# Power_Supply.net
KiCad netlist of a schematic drawn in Altium Designer
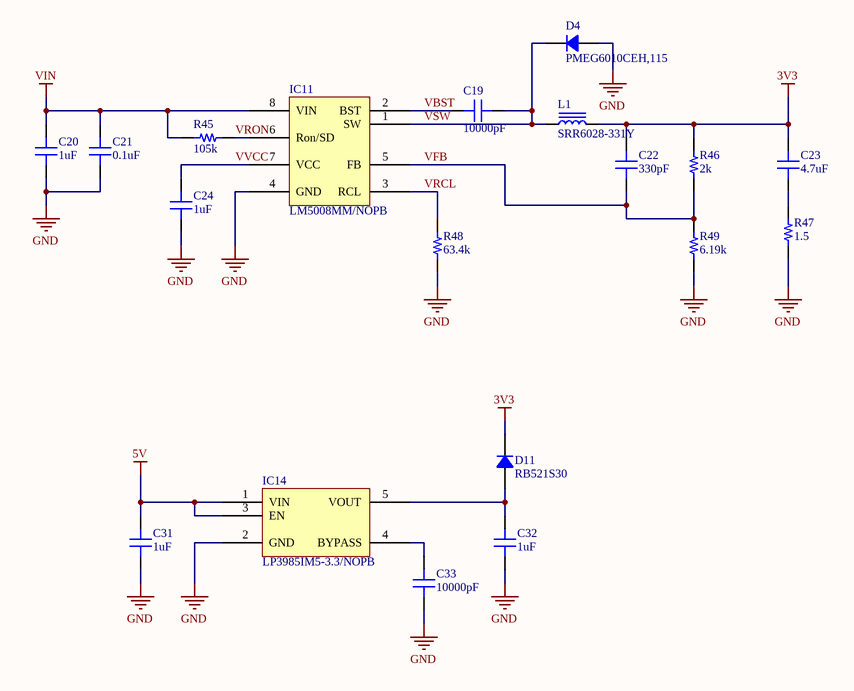
[diagram p0: Power Supply.SchDoc]

(export (version "E")
  (design (tool "Eeschema 10.0.6"))
  (components
    (comp (ref "C19")
      (value "10000pF")
      (footprint "CAP 0603/1608")
      (description "CAP CER 10000PF 50V X7R 0603")
      (fields
        (field (name "PART NUMBER") "CL10B103KB8NCNC")
        (field (name "MANUFACTURER") "Samsung Electro-Mechanics America, Inc.")
      )
      (libsource (lib "Celestial Library Database") (part "Capacitor"))
    )
    (comp (ref "C20")
      (value "1uF")
      (footprint "CAP 0603/1608")
      (description "CAP CER 1UF 50V X5R 0603")
      (fields
        (field (name "PART NUMBER") "CL10A105KB8NNNC")
        (field (name "MANUFACTURER") "Samsung Electro-Mechanics America, Inc.")
      )
      (libsource (lib "Celestial Library Database") (part "Capacitor"))
    )
    (comp (ref "C21")
      (value "0.1uF")
      (footprint "CAP 0603/1608")
      (description "CAP CER 0.1UF 50V X7R 0603")
      (fields
        (field (name "PART NUMBER") "CL10B104JB8NNNC")
        (field (name "MANUFACTURER") "Samsung Electro-Mechanics America, Inc.")
      )
      (libsource (lib "Celestial Library Database") (part "Capacitor"))
    )
    (comp (ref "C22")
      (value "330pF")
      (footprint "CAP 0603/1608")
      (description "CAP CER 330PF 50V NP0 0603")
      (fields (field (name "PART NUMBER") "C0603C331J5GACTU") (field (name "MANUFACTURER") "Kemet"))
      (libsource (lib "Celestial Library Database") (part "Capacitor"))
    )
    (comp (ref "C23")
      (value "4.7uF")
      (footprint "CAP 0603/1608")
      (description "CAP CER 4.7UF 6.3V X5R 0603")
      (fields
        (field (name "PART NUMBER") "CL10A475KQ8NNNC")
        (field (name "MANUFACTURER") "Samsung Electro-Mechanics America, Inc.")
      )
      (libsource (lib "Celestial Library Database") (part "Capacitor"))
    )
    (comp (ref "C24")
      (value "1uF")
      (footprint "CAP 0603/1608")
      (description "CAP CER 1UF 50V X5R 0603")
      (fields
        (field (name "PART NUMBER") "CL10A105KB8NNNC")
        (field (name "MANUFACTURER") "Samsung Electro-Mechanics America, Inc.")
      )
      (libsource (lib "Celestial Library Database") (part "Capacitor"))
    )
    (comp (ref "C31")
      (value "1uF")
      (footprint "CAP 0603/1608")
      (description "CAP CER 1UF 50V X5R 0603")
      (fields
        (field (name "PART NUMBER") "CL10A105KB8NNNC")
        (field (name "MANUFACTURER") "Samsung Electro-Mechanics America, Inc.")
      )
      (libsource (lib "Celestial Library Database") (part "Capacitor"))
    )
    (comp (ref "C32")
      (value "1uF")
      (footprint "CAP 0603/1608")
      (description "CAP CER 1UF 50V X5R 0603")
      (fields
        (field (name "PART NUMBER") "CL10A105KB8NNNC")
        (field (name "MANUFACTURER") "Samsung Electro-Mechanics America, Inc.")
      )
      (libsource (lib "Celestial Library Database") (part "Capacitor"))
    )
    (comp (ref "C33")
      (value "10000pF")
      (footprint "CAP 0603/1608")
      (description "CAP CER 10000PF 50V X7R 0603")
      (fields
        (field (name "PART NUMBER") "CL10B103KB8NCNC")
        (field (name "MANUFACTURER") "Samsung Electro-Mechanics America, Inc.")
      )
      (libsource (lib "Celestial Library Database") (part "Capacitor"))
    )
    (comp (ref "D4")
      (value "PMEG6010CEH,115")
      (footprint "SOD123F")
      (description "DIODE SCHOTTKY 60V 1A SOD123F")
      (fields (field (name "MANUFACTURER") "NXP USA Inc."))
      (libsource (lib "Celestial Library Database") (part "Diode"))
    )
    (comp (ref "D11")
      (value "RB521S30")
      (footprint "SOD523F")
      (description "DIODE SCHOTTKY 30V 200MA SOD523F")
      (fields (field (name "MANUFACTURER") "Fairchild Semiconductor"))
      (libsource (lib "Celestial Library Database") (part "Diode"))
    )
    (comp (ref "IC11")
      (value "LM5008MM/NOPB")
      (footprint "TI VSSOP-8 DGK")
      (description "IC REG BUCK ADJ 0.35A 8VSSOP")
      (fields (field (name "MANUFACTURER") "Texas Instruments"))
      (libsource (lib "Celestial Library Database") (part "TI LM5008"))
    )
    (comp (ref "IC14")
      (value "LP3985IM5-3.3/NOPB")
      (footprint "TI SOT-23-5 DBV")
      (description "IC REG LDO 3.3V 0.15A SOT23-5")
      (fields (field (name "MANUFACTURER") "Texas Instruments"))
      (libsource (lib "Celestial Library Database") (part "TI LP3985"))
    )
    (comp (ref "L1")
      (value "SRR6028-331Y")
      (footprint "BOURNS SRR6028")
      (description "FIXED IND 330UH 370MA 1.4 OHM")
      (fields (field (name "MANUFACTURER") "Bourns Inc.") (field (name "TOLERANCE") "30%"))
      (libsource (lib "Celestial Library Database") (part "Inductor"))
    )
    (comp (ref "R45")
      (value "105k")
      (footprint "RES 0603/1608")
      (description "RES SMD 105K OHM 1% 1/10W 0603")
      (fields
        (field (name "PART NUMBER") "ERJ-3EKF1053V")
        (field (name "MANUFACTURER") "Panasonic Electronic Components")
      )
      (libsource (lib "Celestial Library Database") (part "Resistor"))
    )
    (comp (ref "R46")
      (value "2k")
      (footprint "RES 0603/1608")
      (description "RES SMD 2K OHM 5% 1/10W 0603")
      (fields
        (field (name "PART NUMBER") "ERJ-3GEYJ202V")
        (field (name "MANUFACTURER") "Panasonic Electronic Components")
      )
      (libsource (lib "Celestial Library Database") (part "Resistor"))
    )
    (comp (ref "R47")
      (value "1.5")
      (footprint "RES 0603/1608")
      (description "RES SMD 1.5 OHM 5% 1/10W 0603")
      (fields
        (field (name "PART NUMBER") "ERJ-3GEYJ1R5V")
        (field (name "MANUFACTURER") "Panasonic Electronic Components")
      )
      (libsource (lib "Celestial Library Database") (part "Resistor"))
    )
    (comp (ref "R48")
      (value "63.4k")
      (footprint "RES 0603/1608")
      (description "RES SMD 63.4K OHM 1% 1/10W 0603")
      (fields
        (field (name "PART NUMBER") "ERJ-3EKF6342V")
        (field (name "MANUFACTURER") "Panasonic Electronic Components")
      )
      (libsource (lib "Celestial Library Database") (part "Resistor"))
    )
    (comp (ref "R49")
      (value "6.19k")
      (footprint "RES 0603/1608")
      (description "RES SMD 6.19K OHM 1% 1/10W 0603")
      (fields
        (field (name "PART NUMBER") "ERJ-3EKF6191V")
        (field (name "MANUFACTURER") "Panasonic Electronic Components")
      )
      (libsource (lib "Celestial Library Database") (part "Resistor"))
    )
  )
  (nets
    (net (code "1") (name "/VBST") (class "Default")
      (node (ref "C19") (pin "2") (pinfunction "2_2") (pintype "passive"))
      (node (ref "IC11") (pin "2") (pinfunction "BST_2") (pintype "passive"))
    )
    (net (code "2") (name "/VFB") (class "Default")
      (node (ref "C22") (pin "1") (pinfunction "1_1") (pintype "passive"))
      (node (ref "IC11") (pin "5") (pinfunction "FB_5") (pintype "passive"))
      (node (ref "R46") (pin "2") (pinfunction "2_2") (pintype "passive"))
      (node (ref "R49") (pin "2") (pinfunction "2_2") (pintype "passive"))
    )
    (net (code "3") (name "/VRCL") (class "Default")
      (node (ref "IC11") (pin "3") (pinfunction "RCL_3") (pintype "passive"))
      (node (ref "R48") (pin "2") (pinfunction "2_2") (pintype "passive"))
    )
    (net (code "4") (name "/VRON") (class "Default")
      (node (ref "IC11") (pin "6") (pinfunction "Ron/SD_6") (pintype "passive"))
      (node (ref "R45") (pin "2") (pinfunction "2_2") (pintype "passive"))
    )
    (net (code "5") (name "/VSW") (class "Default")
      (node (ref "C19") (pin "1") (pinfunction "1_1") (pintype "passive"))
      (node (ref "D4") (pin "2") (pinfunction "2_2") (pintype "passive"))
      (node (ref "IC11") (pin "1") (pinfunction "SW_1") (pintype "passive"))
      (node (ref "L1") (pin "1") (pinfunction "1_1") (pintype "passive"))
    )
    (net (code "6") (name "/VVCC") (class "Default")
      (node (ref "C24") (pin "2") (pinfunction "2_2") (pintype "passive"))
      (node (ref "IC11") (pin "7") (pinfunction "VCC_7") (pintype "passive"))
    )
    (net (code "7") (name "3V3") (class "Default")
      (node (ref "C22") (pin "2") (pinfunction "2_2") (pintype "passive"))
      (node (ref "C23") (pin "2") (pinfunction "2_2") (pintype "passive"))
      (node (ref "D11") (pin "2") (pinfunction "2_2") (pintype "passive"))
      (node (ref "L1") (pin "2") (pinfunction "2_2") (pintype "passive"))
      (node (ref "R46") (pin "1") (pinfunction "1_1") (pintype "passive"))
    )
    (net (code "8") (name "5V") (class "Default")
      (node (ref "C31") (pin "2") (pinfunction "2_2") (pintype "passive"))
      (node (ref "IC14") (pin "1") (pinfunction "VIN_1") (pintype "passive"))
      (node (ref "IC14") (pin "3") (pinfunction "EN_3") (pintype "passive"))
    )
    (net (code "9") (name "GND") (class "Default")
      (node (ref "C20") (pin "1") (pinfunction "1_1") (pintype "passive"))
      (node (ref "C21") (pin "2") (pinfunction "2_2") (pintype "passive"))
      (node (ref "C24") (pin "1") (pinfunction "1_1") (pintype "passive"))
      (node (ref "C31") (pin "1") (pinfunction "1_1") (pintype "passive"))
      (node (ref "C32") (pin "1") (pinfunction "1_1") (pintype "passive"))
      (node (ref "C33") (pin "1") (pinfunction "1_1") (pintype "passive"))
      (node (ref "D4") (pin "1") (pinfunction "1_1") (pintype "passive"))
      (node (ref "IC11") (pin "4") (pinfunction "GND_4") (pintype "passive"))
      (node (ref "IC14") (pin "2") (pinfunction "GND_2") (pintype "passive"))
      (node (ref "R47") (pin "1") (pinfunction "1_1") (pintype "passive"))
      (node (ref "R48") (pin "1") (pinfunction "1_1") (pintype "passive"))
      (node (ref "R49") (pin "1") (pinfunction "1_1") (pintype "passive"))
    )
    (net (code "10") (name "Net-(C23-Pad1)") (class "Default")
      (node (ref "C23") (pin "1") (pinfunction "1_1") (pintype "passive"))
      (node (ref "R47") (pin "2") (pinfunction "2_2") (pintype "passive"))
    )
    (net (code "11") (name "Net-(IC14-BYPASS)") (class "Default")
      (node (ref "C33") (pin "2") (pinfunction "2_2") (pintype "passive"))
      (node (ref "IC14") (pin "4") (pinfunction "BYPASS_4") (pintype "passive"))
    )
    (net (code "12") (name "Net-(IC14-VOUT)") (class "Default")
      (node (ref "C32") (pin "2") (pinfunction "2_2") (pintype "passive"))
      (node (ref "D11") (pin "1") (pinfunction "1_1") (pintype "passive"))
      (node (ref "IC14") (pin "5") (pinfunction "VOUT_5") (pintype "passive"))
    )
    (net (code "13") (name "VIN") (class "Default")
      (node (ref "C20") (pin "2") (pinfunction "2_2") (pintype "passive"))
      (node (ref "C21") (pin "1") (pinfunction "1_1") (pintype "passive"))
      (node (ref "IC11") (pin "8") (pinfunction "VIN_8") (pintype "passive"))
      (node (ref "R45") (pin "1") (pinfunction "1_1") (pintype "passive"))
    )
  )
)
